# soil_temp_v0_2.net
KiCad netlist of a schematic drawn in EAGLE
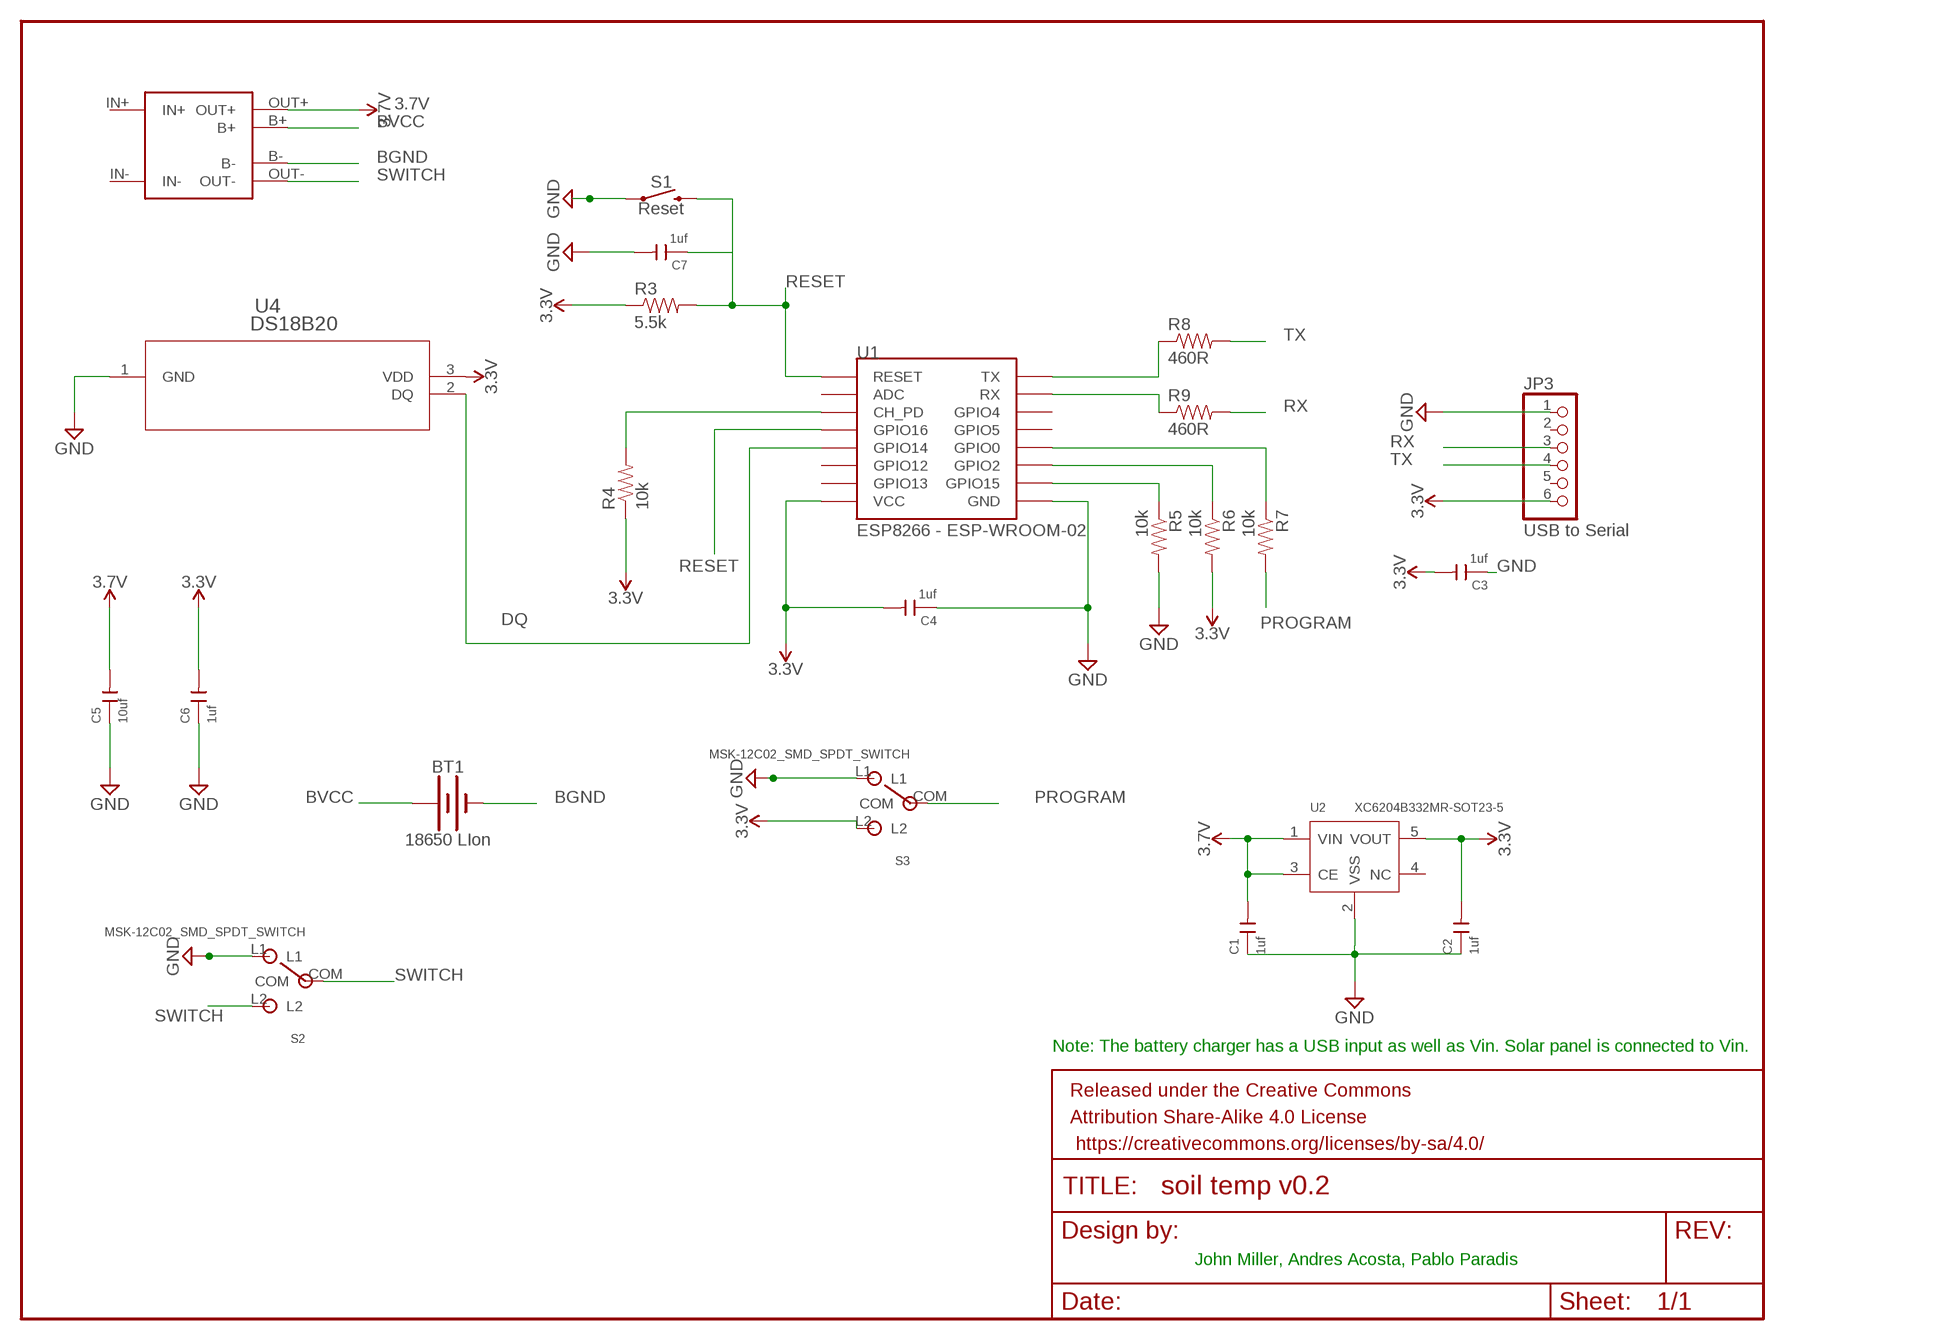
[diagram p0: schematic, sheet 1]

(export (version "E")
  (design (tool "Eeschema 10.0.6"))
  (components
    (comp (ref "BT1")
      (value "18650 LIon")
      (footprint "eagle-import:BATTERY_18650-HOLDER")
      (libsource (lib "eagle-import") (part "BATTERY-18650"))
    )
    (comp (ref "C1")
      (value "1uf")
      (footprint "eagle-import:C0805")
      (fields (field (name "MPN") "CC0805KKX7R8BB105"))
      (libsource (lib "eagle-import") (part "CERAMIC-1UF-25V-10%-X7R(0805)"))
    )
    (comp (ref "C2")
      (value "1uf")
      (footprint "eagle-import:C0805")
      (fields (field (name "MPN") "CC0805KKX7R8BB105"))
      (libsource (lib "eagle-import") (part "CERAMIC-1UF-25V-10%-X7R(0805)"))
    )
    (comp (ref "C3")
      (value "1uf")
      (footprint "eagle-import:C0805")
      (fields (field (name "MPN") "CC0805KKX7R8BB105"))
      (libsource (lib "eagle-import") (part "CERAMIC-1UF-25V-10%-X7R(0805)"))
    )
    (comp (ref "C4")
      (value "1uf")
      (footprint "eagle-import:C0805")
      (fields (field (name "MPN") "CC0805KKX7R8BB105"))
      (libsource (lib "eagle-import") (part "CERAMIC-1UF-25V-10%-X7R(0805)"))
    )
    (comp (ref "C5")
      (value "10uf")
      (footprint "eagle-import:C0805")
      (fields (field (name "MPN") "CC0805KKX7R8BB105"))
      (libsource (lib "eagle-import") (part "CERAMIC-1UF-25V-10%-X7R(0805)"))
    )
    (comp (ref "C6")
      (value "1uf")
      (footprint "eagle-import:C0805")
      (fields (field (name "MPN") "CC0805KKX7R8BB105"))
      (libsource (lib "eagle-import") (part "CERAMIC-1UF-25V-10%-X7R(0805)"))
    )
    (comp (ref "C7")
      (value "1uf")
      (footprint "eagle-import:C0805")
      (fields (field (name "MPN") "CC0805KKX7R8BB105"))
      (libsource (lib "eagle-import") (part "CERAMIC-1UF-25V-10%-X7R(0805)"))
    )
    (comp (ref "FRAME1")
      (value "FRAME-LETTERNO_PACKAGE")
      (footprint "eagle-import:DUMMY")
      (fields (field (name "DESIGNER") "Nobody"))
      (libsource (lib "eagle-import") (part "FRAME-LETTERNO_PACKAGE"))
    )
    (comp (ref "JP3")
      (value "USB to Serial")
      (footprint "eagle-import:1X06_90")
      (libsource (lib "eagle-import") (part "PINHD-1X6/90"))
    )
    (comp (ref "R3")
      (value "5.5k")
      (footprint "eagle-import:R0805")
      (libsource (lib "eagle-import") (part "RESISTOR0805"))
    )
    (comp (ref "R4")
      (value "10k")
      (footprint "eagle-import:R0805")
      (libsource (lib "eagle-import") (part "RESISTOR0805"))
    )
    (comp (ref "R5")
      (value "10k")
      (footprint "eagle-import:R0805")
      (libsource (lib "eagle-import") (part "RESISTOR0805"))
    )
    (comp (ref "R6")
      (value "10k")
      (footprint "eagle-import:R0805")
      (libsource (lib "eagle-import") (part "RESISTOR0805"))
    )
    (comp (ref "R7")
      (value "10k")
      (footprint "eagle-import:R0805")
      (libsource (lib "eagle-import") (part "RESISTOR0805"))
    )
    (comp (ref "R8")
      (value "460R")
      (footprint "eagle-import:R0805")
      (libsource (lib "eagle-import") (part "RESISTOR0805"))
    )
    (comp (ref "R9")
      (value "460R")
      (footprint "eagle-import:R0805")
      (libsource (lib "eagle-import") (part "RESISTOR0805"))
    )
    (comp (ref "S1")
      (value "Reset")
      (footprint "eagle-import:TACTILE_SWITCH_SMD_6.2MM_TALL")
      (libsource (lib "eagle-import") (part "MOMENTARY-SWITCH-SPST-SMD-6.2MM-TALL"))
    )
    (comp (ref "S2")
      (value "MSK-12C02_SMD_SPDT_SWITCH")
      (footprint "eagle-import:MSK-12C02")
      (libsource (lib "eagle-import") (part "MSK-12C02_SMD_SPDT_SWITCH"))
    )
    (comp (ref "S3")
      (value "MSK-12C02_SMD_SPDT_SWITCH")
      (footprint "eagle-import:MSK-12C02")
      (libsource (lib "eagle-import") (part "MSK-12C02_SMD_SPDT_SWITCH"))
    )
    (comp (ref "U1")
      (value "ESP8266 - ESP-WROOM-02")
      (footprint "eagle-import:ESP12")
      (libsource (lib "eagle-import") (part "ESP12"))
    )
    (comp (ref "U2")
      (value "XC6204B332MR-SOT23-5")
      (footprint "eagle-import:SOT-23-5")
      (fields (field (name "MPN") "XC6204B332MR"))
      (libsource (lib "eagle-import") (part "PMIC-LDO-XC6204B332MR(SOT23-5)"))
    )
    (comp (ref "U3")
      (value "TP4056-MODULE")
      (footprint "eagle-import:TP4056-LITHIUM-PROTECTED-MODULE")
      (libsource (lib "eagle-import") (part "TP4056-MODULE"))
    )
    (comp (ref "U4")
      (value "DS18B20")
      (footprint "eagle-import:21-0248A")
      (libsource (lib "eagle-import") (part "DS18B20"))
    )
  )
  (nets
    (net (code "1") (name "/BGND") (class "Default")
      (node (ref "BT1") (pin "GND@1") (pinfunction "-_GND@1") (pintype "power_in"))
      (node (ref "U3") (pin "B-") (pinfunction "B-_B-") (pintype "power_in"))
    )
    (net (code "2") (name "/BVCC") (class "Default")
      (node (ref "BT1") (pin "PWR@1") (pinfunction "+_PWR@1") (pintype "power_in"))
      (node (ref "U3") (pin "B+") (pinfunction "B+_B+") (pintype "power_in"))
    )
    (net (code "3") (name "/DQ") (class "Default")
      (node (ref "U1") (pin "GPIO14") (pinfunction "GPIO14_GPIO14") (pintype "bidirectional"))
      (node (ref "U4") (pin "2") (pinfunction "DQ_2") (pintype "bidirectional"))
    )
    (net (code "4") (name "/IN+") (class "Default")
      (node (ref "U3") (pin "IN+") (pinfunction "IN+_IN+") (pintype "power_in"))
    )
    (net (code "5") (name "/IN-") (class "Default")
      (node (ref "U3") (pin "IN-") (pinfunction "IN-_IN-") (pintype "power_in"))
    )
    (net (code "6") (name "/PROGRAM") (class "Default")
      (node (ref "R7") (pin "2") (pinfunction "2_2") (pintype "passive"))
      (node (ref "S3") (pin "COM") (pinfunction "COM_COM") (pintype "bidirectional"))
    )
    (net (code "7") (name "/RESET") (class "Default")
      (node (ref "C7") (pin "1") (pinfunction "1_1") (pintype "passive"))
      (node (ref "R3") (pin "2") (pinfunction "2_2") (pintype "passive"))
      (node (ref "S1") (pin "B2") (pinfunction "2_B2") (pintype "passive"))
      (node (ref "U1") (pin "GPIO16") (pinfunction "GPIO16_GPIO16") (pintype "bidirectional"))
      (node (ref "U1") (pin "RESET") (pinfunction "RESET_RESET") (pintype "bidirectional"))
    )
    (net (code "8") (name "/RX") (class "Default")
      (node (ref "JP3") (pin "3") (pinfunction "3_3") (pintype "passive"))
      (node (ref "R9") (pin "2") (pinfunction "2_2") (pintype "passive"))
    )
    (net (code "9") (name "/SWITCH") (class "Default")
      (node (ref "S2") (pin "COM") (pinfunction "COM_COM") (pintype "bidirectional"))
      (node (ref "S2") (pin "L2") (pinfunction "L2_L2") (pintype "bidirectional"))
      (node (ref "U3") (pin "OUT-") (pinfunction "OUT-_OUT-") (pintype "power_in"))
    )
    (net (code "10") (name "/TX") (class "Default")
      (node (ref "JP3") (pin "4") (pinfunction "4_4") (pintype "passive"))
      (node (ref "R8") (pin "2") (pinfunction "2_2") (pintype "passive"))
    )
    (net (code "11") (name "3.3V") (class "Default")
      (node (ref "C2") (pin "2") (pinfunction "2_2") (pintype "passive"))
      (node (ref "C3") (pin "2") (pinfunction "2_2") (pintype "passive"))
      (node (ref "C4") (pin "2") (pinfunction "2_2") (pintype "passive"))
      (node (ref "C6") (pin "2") (pinfunction "2_2") (pintype "passive"))
      (node (ref "JP3") (pin "6") (pinfunction "6_6") (pintype "passive"))
      (node (ref "R3") (pin "1") (pinfunction "1_1") (pintype "passive"))
      (node (ref "R4") (pin "1") (pinfunction "1_1") (pintype "passive"))
      (node (ref "R6") (pin "2") (pinfunction "2_2") (pintype "passive"))
      (node (ref "S3") (pin "L2") (pinfunction "L2_L2") (pintype "bidirectional"))
      (node (ref "U1") (pin "VCC") (pinfunction "VCC_VCC") (pintype "bidirectional"))
      (node (ref "U2") (pin "5") (pinfunction "VOUT_5") (pintype "output"))
      (node (ref "U4") (pin "3") (pinfunction "VDD_3") (pintype "power_in"))
    )
    (net (code "12") (name "3.7V") (class "Default")
      (node (ref "C1") (pin "2") (pinfunction "2_2") (pintype "passive"))
      (node (ref "C5") (pin "2") (pinfunction "2_2") (pintype "passive"))
      (node (ref "U2") (pin "1") (pinfunction "VIN_1") (pintype "input"))
      (node (ref "U2") (pin "3") (pinfunction "CE_3") (pintype "bidirectional"))
      (node (ref "U3") (pin "OUT+") (pinfunction "OUT+_OUT+") (pintype "power_in"))
    )
    (net (code "13") (name "GND") (class "Default")
      (node (ref "C1") (pin "1") (pinfunction "1_1") (pintype "passive"))
      (node (ref "C2") (pin "1") (pinfunction "1_1") (pintype "passive"))
      (node (ref "C3") (pin "1") (pinfunction "1_1") (pintype "passive"))
      (node (ref "C4") (pin "1") (pinfunction "1_1") (pintype "passive"))
      (node (ref "C5") (pin "1") (pinfunction "1_1") (pintype "passive"))
      (node (ref "C6") (pin "1") (pinfunction "1_1") (pintype "passive"))
      (node (ref "C7") (pin "2") (pinfunction "2_2") (pintype "passive"))
      (node (ref "JP3") (pin "1") (pinfunction "1_1") (pintype "passive"))
      (node (ref "R5") (pin "2") (pinfunction "2_2") (pintype "passive"))
      (node (ref "S1") (pin "A2") (pinfunction "1_A2") (pintype "passive"))
      (node (ref "S2") (pin "L1") (pinfunction "L1_L1") (pintype "bidirectional"))
      (node (ref "S3") (pin "L1") (pinfunction "L1_L1") (pintype "bidirectional"))
      (node (ref "U1") (pin "GND") (pinfunction "GND_GND") (pintype "bidirectional"))
      (node (ref "U2") (pin "2") (pinfunction "VSS_2") (pintype "power_in"))
      (node (ref "U4") (pin "1") (pinfunction "GND_1") (pintype "power_in"))
    )
    (net (code "14") (name "Net-(R4-Pad2)") (class "Default")
      (node (ref "R4") (pin "2") (pinfunction "2_2") (pintype "passive"))
      (node (ref "U1") (pin "CH_PD") (pinfunction "CH_PD_CH_PD") (pintype "bidirectional"))
    )
    (net (code "15") (name "Net-(R5-Pad1)") (class "Default")
      (node (ref "R5") (pin "1") (pinfunction "1_1") (pintype "passive"))
      (node (ref "U1") (pin "GPIO15") (pinfunction "GPIO15_GPIO15") (pintype "bidirectional"))
    )
    (net (code "16") (name "Net-(R6-Pad1)") (class "Default")
      (node (ref "R6") (pin "1") (pinfunction "1_1") (pintype "passive"))
      (node (ref "U1") (pin "GPIO2") (pinfunction "GPIO2_GPIO2") (pintype "bidirectional"))
    )
    (net (code "17") (name "Net-(R7-Pad1)") (class "Default")
      (node (ref "R7") (pin "1") (pinfunction "1_1") (pintype "passive"))
      (node (ref "U1") (pin "GPIO0") (pinfunction "GPIO0_GPIO0") (pintype "bidirectional"))
    )
    (net (code "18") (name "Net-(R8-Pad1)") (class "Default")
      (node (ref "R8") (pin "1") (pinfunction "1_1") (pintype "passive"))
      (node (ref "U1") (pin "TX") (pinfunction "TX_TX") (pintype "bidirectional"))
    )
    (net (code "19") (name "Net-(R9-Pad1)") (class "Default")
      (node (ref "R9") (pin "1") (pinfunction "1_1") (pintype "passive"))
      (node (ref "U1") (pin "RX") (pinfunction "RX_RX") (pintype "bidirectional"))
    )
    (net (code "20") (name "unconnected-(JP3-Pad2)") (class "Default")
      (node (ref "JP3") (pin "2") (pinfunction "2_2") (pintype "passive"))
    )
    (net (code "21") (name "unconnected-(JP3-Pad5)") (class "Default")
      (node (ref "JP3") (pin "5") (pinfunction "5_5") (pintype "passive"))
    )
    (net (code "22") (name "unconnected-(U1-PadADC)") (class "Default")
      (node (ref "U1") (pin "ADC") (pinfunction "ADC_ADC") (pintype "bidirectional"))
    )
    (net (code "23") (name "unconnected-(U1-PadGPIO4)") (class "Default")
      (node (ref "U1") (pin "GPIO4") (pinfunction "GPIO4_GPIO4") (pintype "bidirectional"))
    )
    (net (code "24") (name "unconnected-(U1-PadGPIO5)") (class "Default")
      (node (ref "U1") (pin "GPIO5") (pinfunction "GPIO5_GPIO5") (pintype "bidirectional"))
    )
    (net (code "25") (name "unconnected-(U1-PadGPIO12)") (class "Default")
      (node (ref "U1") (pin "GPIO12") (pinfunction "GPIO12_GPIO12") (pintype "bidirectional"))
    )
    (net (code "26") (name "unconnected-(U1-PadGPIO13)") (class "Default")
      (node (ref "U1") (pin "GPIO13") (pinfunction "GPIO13_GPIO13") (pintype "bidirectional"))
    )
    (net (code "27") (name "unconnected-(U2-NC-Pad4)") (class "Default")
      (node (ref "U2") (pin "4") (pinfunction "NC_4") (pintype "no_connect"))
    )
  )
)
